# semi-controlled-rectifier-breakout-board.net
KiCad netlist of a schematic drawn in EAGLE
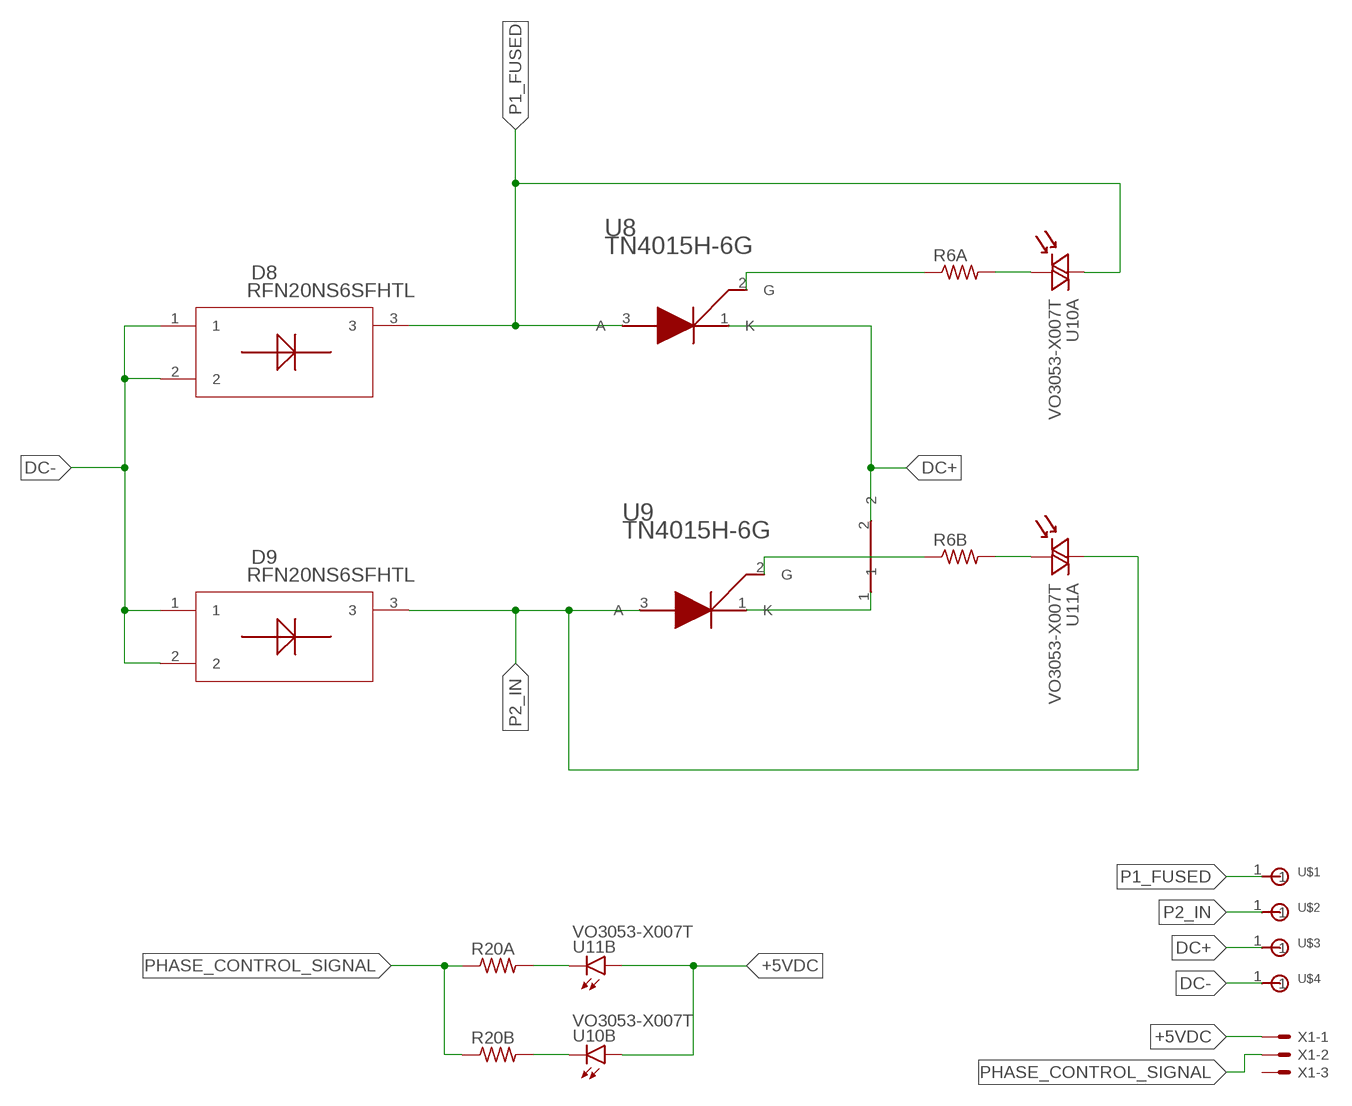
[diagram p0: schematic, sheet 1]

(export (version "E")
  (design (tool "Eeschema 10.0.6"))
  (components
    (comp (ref "D8")
      (value "RFN20NS6SFHTL")
      (footprint "eagle-import:DIO_RFN10N_ROM-M")
      (fields (field (name "COPYRIGHT") "Copyright (C) 2022 Ultra Librarian. All rights reserved."))
      (libsource (lib "eagle-import") (part "RFN20NS6SFHTLDIO_RFN10N_ROM-M"))
    )
    (comp (ref "D9")
      (value "RFN20NS6SFHTL")
      (footprint "eagle-import:DIO_RFN10N_ROM-M")
      (fields (field (name "COPYRIGHT") "Copyright (C) 2022 Ultra Librarian. All rights reserved."))
      (libsource (lib "eagle-import") (part "RFN20NS6SFHTLDIO_RFN10N_ROM-M"))
    )
    (comp (ref "R6A")
      (value "R-US_0207/7")
      (footprint "eagle-import:0207_7")
      (libsource (lib "eagle-import") (part "R-US_0207/7"))
    )
    (comp (ref "R6B")
      (value "R-US_0207/7")
      (footprint "eagle-import:0207_7")
      (libsource (lib "eagle-import") (part "R-US_0207/7"))
    )
    (comp (ref "R20A")
      (value "R-US_0207/7")
      (footprint "eagle-import:0207_7")
      (libsource (lib "eagle-import") (part "R-US_0207/7"))
    )
    (comp (ref "R20B")
      (value "R-US_0207/7")
      (footprint "eagle-import:0207_7")
      (libsource (lib "eagle-import") (part "R-US_0207/7"))
    )
    (comp (ref "U$1")
      (value "90MIL_TERMINAL")
      (footprint "eagle-import:90MIL_TERMINAL")
      (libsource (lib "eagle-import") (part "90MIL_TERMINAL"))
    )
    (comp (ref "U$2")
      (value "90MIL_TERMINAL")
      (footprint "eagle-import:90MIL_TERMINAL")
      (libsource (lib "eagle-import") (part "90MIL_TERMINAL"))
    )
    (comp (ref "U$3")
      (value "90MIL_TERMINAL")
      (footprint "eagle-import:90MIL_TERMINAL")
      (libsource (lib "eagle-import") (part "90MIL_TERMINAL"))
    )
    (comp (ref "U$4")
      (value "90MIL_TERMINAL")
      (footprint "eagle-import:90MIL_TERMINAL")
      (libsource (lib "eagle-import") (part "90MIL_TERMINAL"))
    )
    (comp (ref "U$5")
      (value "1000MIL_JUMPER")
      (footprint "eagle-import:1000MIL_JUMPER")
      (libsource (lib "eagle-import") (part "1000MIL_JUMPER"))
    )
    (comp (ref "U8")
      (value "TN4015H-6G")
      (footprint "eagle-import:DIO_RFN10N_ROM-M")
      (libsource (lib "eagle-import") (part "TN4015H-6G"))
    )
    (comp (ref "U9")
      (value "TN4015H-6G")
      (footprint "eagle-import:DIO_RFN10N_ROM-M")
      (libsource (lib "eagle-import") (part "TN4015H-6G"))
    )
    (comp (ref "U10")
      (value "VO3053-X007T")
      (footprint "eagle-import:SOIC254P1030X460-6N")
      (libsource (lib "eagle-import") (part "VO3053-X007T"))
    )
    (comp (ref "U11")
      (value "VO3053-X007T")
      (footprint "eagle-import:SOIC254P1030X460-6N")
      (libsource (lib "eagle-import") (part "VO3053-X007T"))
    )
    (comp (ref "X1")
      (value "22-23-2031")
      (footprint "eagle-import:22-23-2031")
      (fields (field (name "MF") "MOLEX"))
      (libsource (lib "eagle-import") (part "22-23-2031"))
    )
  )
  (nets
    (net (code "1") (name "+5VDC") (class "Default")
      (node (ref "U10") (pin "1") (pinfunction "A_1") (pintype "passive"))
      (node (ref "U11") (pin "1") (pinfunction "A_1") (pintype "passive"))
      (node (ref "X1") (pin "1") (pinfunction "S_1") (pintype "passive"))
    )
    (net (code "2") (name "DC+") (class "Default")
      (node (ref "U$3") (pin "1") (pinfunction "1_1") (pintype "passive"))
      (node (ref "U$5") (pin "2") (pinfunction "2_2") (pintype "passive"))
      (node (ref "U8") (pin "1") (pinfunction "K_1") (pintype "power_in"))
    )
    (net (code "3") (name "DC-") (class "Default")
      (node (ref "D8") (pin "1") (pinfunction "1_1") (pintype "passive"))
      (node (ref "D8") (pin "2") (pinfunction "2_2") (pintype "passive"))
      (node (ref "D9") (pin "1") (pinfunction "1_1") (pintype "passive"))
      (node (ref "D9") (pin "2") (pinfunction "2_2") (pintype "passive"))
      (node (ref "U$4") (pin "1") (pinfunction "1_1") (pintype "passive"))
    )
    (net (code "4") (name "Net-(U8-G)") (class "Default")
      (node (ref "R6A") (pin "1") (pinfunction "1_1") (pintype "passive"))
      (node (ref "U8") (pin "2") (pinfunction "G_2") (pintype "input"))
    )
    (net (code "5") (name "Net-(U9-G)") (class "Default")
      (node (ref "R6B") (pin "1") (pinfunction "1_1") (pintype "passive"))
      (node (ref "U9") (pin "2") (pinfunction "G_2") (pintype "input"))
    )
    (net (code "6") (name "Net-(U9-K)") (class "Default")
      (node (ref "U$5") (pin "1") (pinfunction "1_1") (pintype "passive"))
      (node (ref "U9") (pin "1") (pinfunction "K_1") (pintype "power_in"))
    )
    (net (code "7") (name "Net-(U10A-A1)") (class "Default")
      (node (ref "R6A") (pin "2") (pinfunction "2_2") (pintype "passive"))
      (node (ref "U10") (pin "4") (pinfunction "A1_4") (pintype "passive"))
    )
    (net (code "8") (name "Net-(U10B-C)") (class "Default")
      (node (ref "R20B") (pin "2") (pinfunction "2_2") (pintype "passive"))
      (node (ref "U10") (pin "2") (pinfunction "C_2") (pintype "passive"))
    )
    (net (code "9") (name "Net-(U11A-A1)") (class "Default")
      (node (ref "R6B") (pin "2") (pinfunction "2_2") (pintype "passive"))
      (node (ref "U11") (pin "4") (pinfunction "A1_4") (pintype "passive"))
    )
    (net (code "10") (name "Net-(U11B-C)") (class "Default")
      (node (ref "R20A") (pin "2") (pinfunction "2_2") (pintype "passive"))
      (node (ref "U11") (pin "2") (pinfunction "C_2") (pintype "passive"))
    )
    (net (code "11") (name "P1_FUSED") (class "Default")
      (node (ref "D8") (pin "3") (pinfunction "3_3") (pintype "passive"))
      (node (ref "U$1") (pin "1") (pinfunction "1_1") (pintype "passive"))
      (node (ref "U10") (pin "6") (pinfunction "A2_6") (pintype "passive"))
      (node (ref "U8") (pin "3") (pinfunction "A_3") (pintype "input"))
    )
    (net (code "12") (name "P2_IN") (class "Default")
      (node (ref "D9") (pin "3") (pinfunction "3_3") (pintype "passive"))
      (node (ref "U$2") (pin "1") (pinfunction "1_1") (pintype "passive"))
      (node (ref "U11") (pin "6") (pinfunction "A2_6") (pintype "passive"))
      (node (ref "U9") (pin "3") (pinfunction "A_3") (pintype "input"))
    )
    (net (code "13") (name "PHASE_CONTROL_SIGNAL") (class "Default")
      (node (ref "R20A") (pin "1") (pinfunction "1_1") (pintype "passive"))
      (node (ref "R20B") (pin "1") (pinfunction "1_1") (pintype "passive"))
      (node (ref "X1") (pin "2") (pinfunction "S_2") (pintype "passive"))
    )
    (net (code "14") (name "unconnected-(X1C-S-Pad3)") (class "Default")
      (node (ref "X1") (pin "3") (pinfunction "S_3") (pintype "passive"))
    )
  )
)
